# EYEO_Flower3_Sch.net
KiCad netlist of a schematic drawn in EAGLE
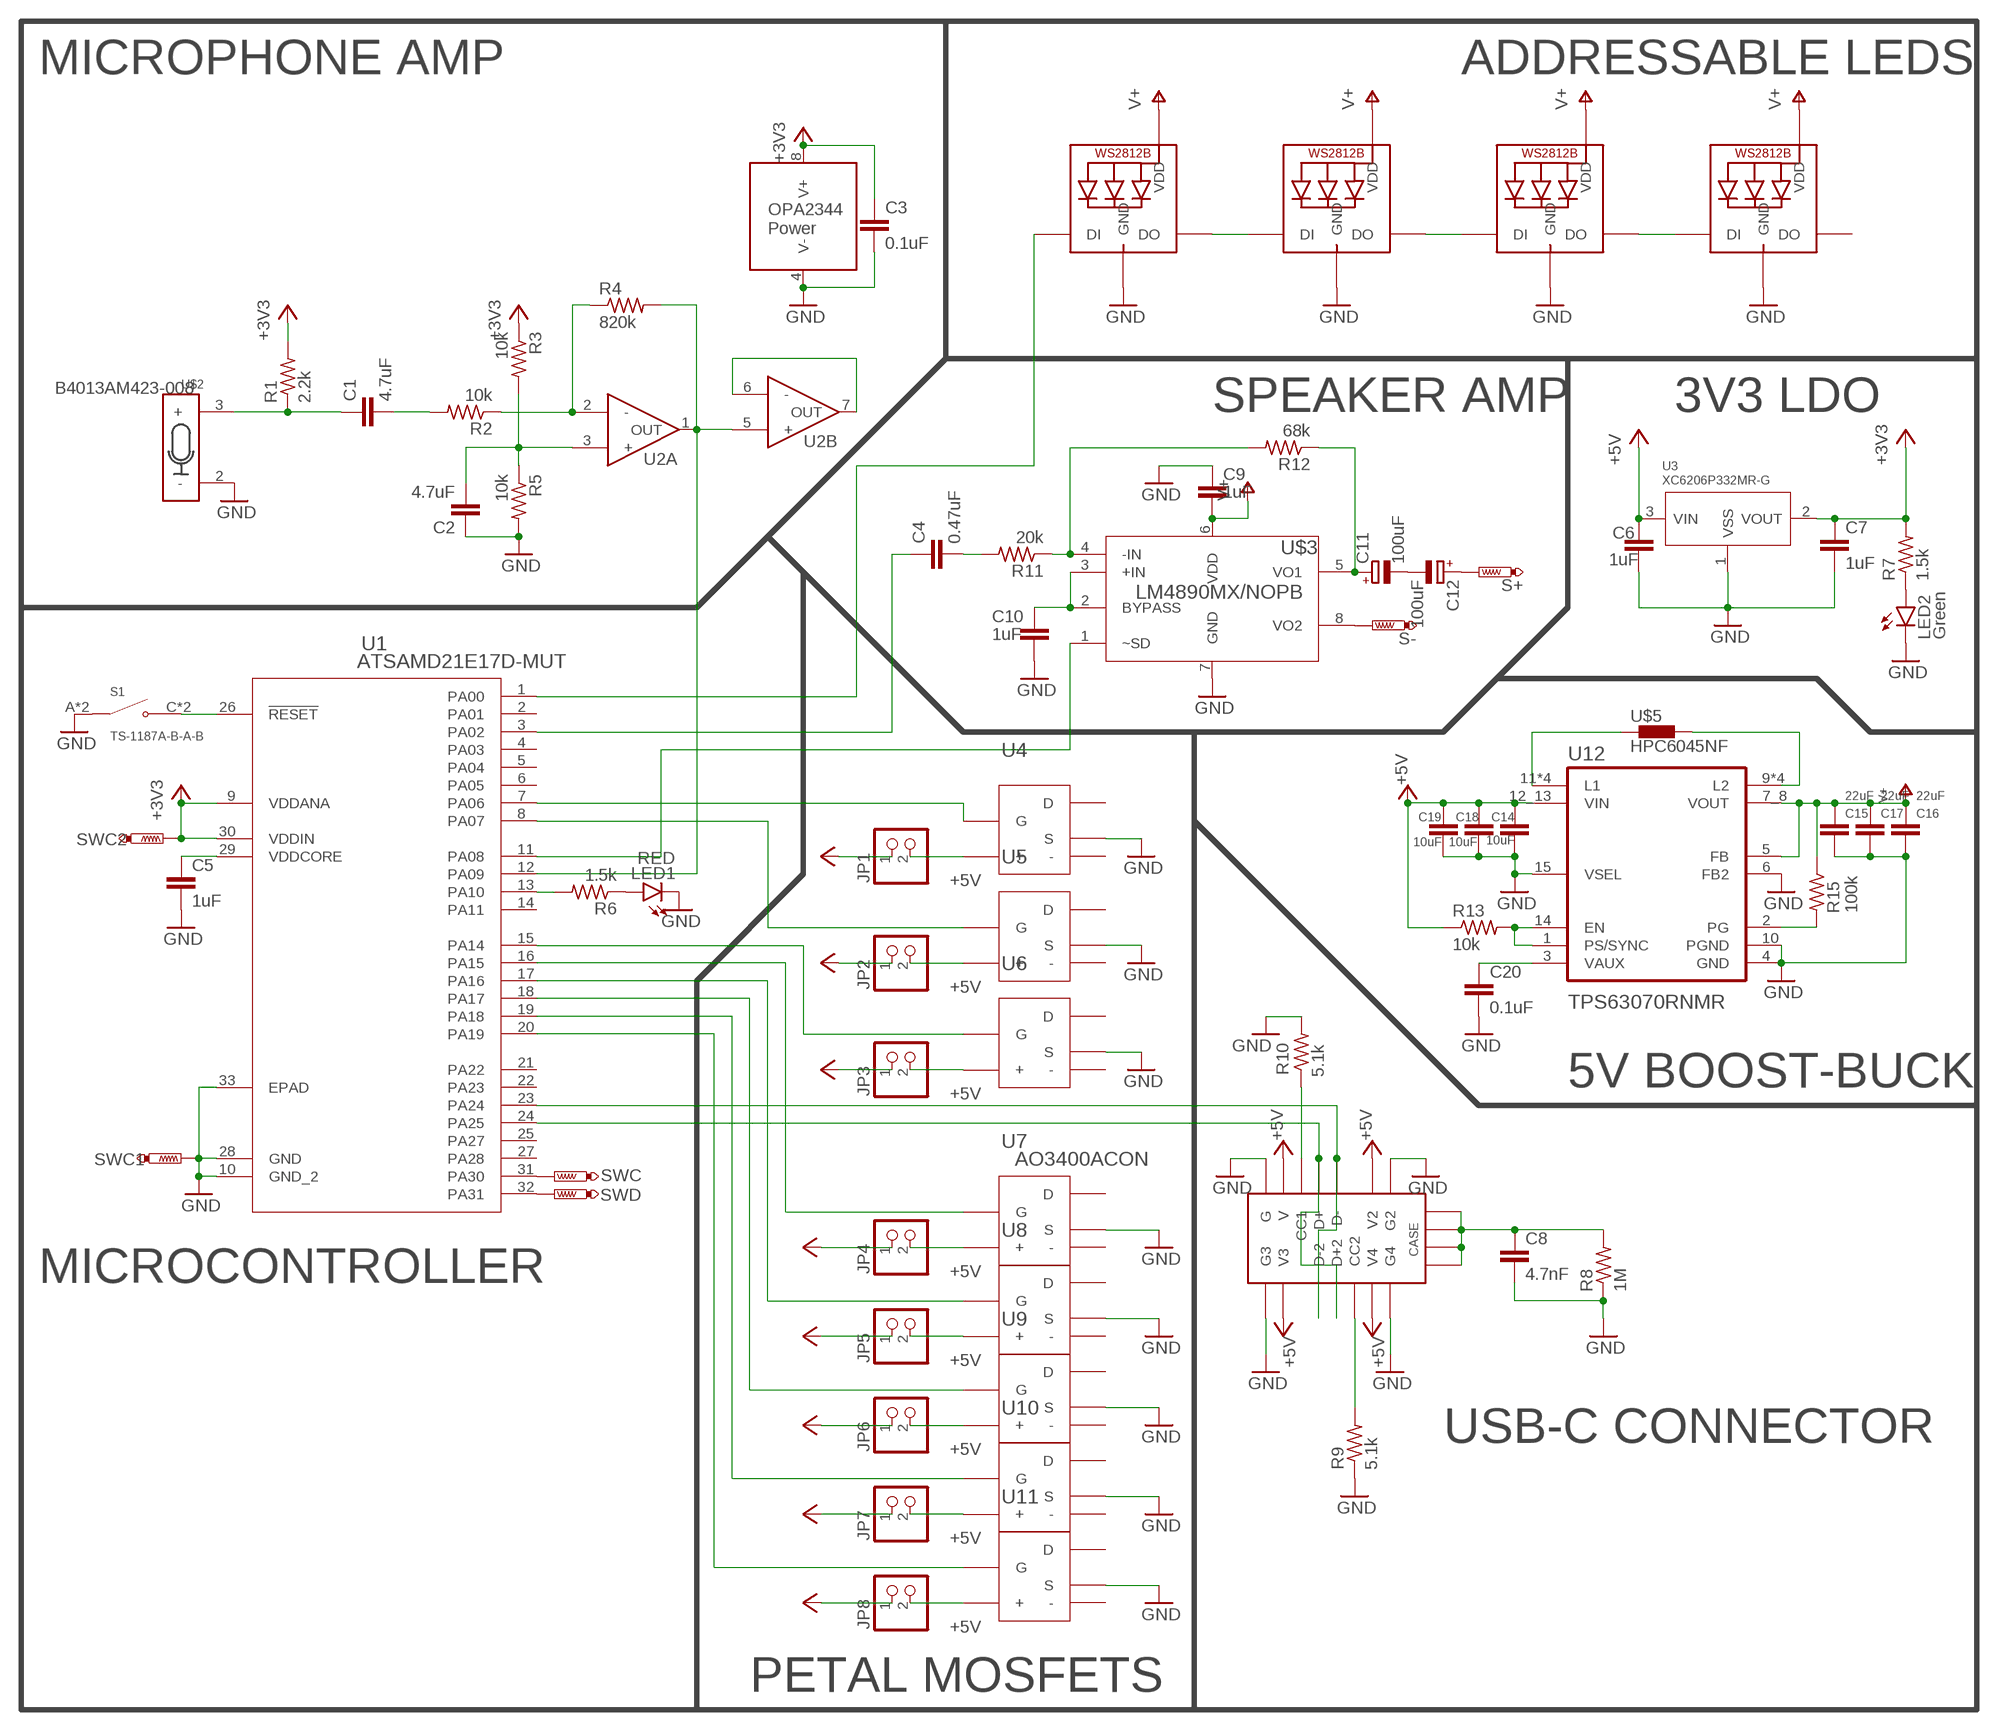
[diagram p0: schematic, sheet 1]

(export (version "E")
  (design (tool "Eeschema 10.0.6"))
  (components
    (comp (ref "C1")
      (value "4.7uF")
      (footprint "eagle-import:C0603")
      (fields (field (name "LCSC_PART") "C19666"))
      (libsource (lib "eagle-import") (part "C-EUC0603"))
    )
    (comp (ref "C2")
      (value "4.7uF")
      (footprint "eagle-import:C0603")
      (fields (field (name "LCSC_PART") "C19666"))
      (libsource (lib "eagle-import") (part "C-EUC0603"))
    )
    (comp (ref "C3")
      (value "0.1uF")
      (footprint "eagle-import:C0402")
      (fields (field (name "LCSC_PART") "C307331"))
      (libsource (lib "eagle-import") (part "C-EUC0402"))
    )
    (comp (ref "C4")
      (value "0.47uF")
      (footprint "eagle-import:C0603")
      (fields (field (name "LCSC_PART") "C1623"))
      (libsource (lib "eagle-import") (part "C-EUC0603"))
    )
    (comp (ref "C5")
      (value "1uF")
      (footprint "eagle-import:C0603")
      (fields (field (name "LCSC_PART") "C15849"))
      (libsource (lib "eagle-import") (part "C-EUC0603"))
    )
    (comp (ref "C6")
      (value "1uF")
      (footprint "eagle-import:C0603")
      (fields (field (name "LCSC_PART") "C15849"))
      (libsource (lib "eagle-import") (part "C-EUC0603"))
    )
    (comp (ref "C7")
      (value "1uF")
      (footprint "eagle-import:C0603")
      (fields (field (name "LCSC_PART") "C15849"))
      (libsource (lib "eagle-import") (part "C-EUC0603"))
    )
    (comp (ref "C8")
      (value "4.7nF")
      (footprint "eagle-import:C0402")
      (fields (field (name "LCSC_PART") "C1538"))
      (libsource (lib "eagle-import") (part "C-EUC0402"))
    )
    (comp (ref "C9")
      (value "1uF")
      (footprint "eagle-import:C0603")
      (fields (field (name "LCSC_PART") "C15849"))
      (libsource (lib "eagle-import") (part "C-EUC0603"))
    )
    (comp (ref "C10")
      (value "1uF")
      (footprint "eagle-import:C0603")
      (fields (field (name "LCSC_PART") "C15849"))
      (libsource (lib "eagle-import") (part "C-EUC0603"))
    )
    (comp (ref "C11")
      (value "100uF")
      (footprint "eagle-import:153CLV-0505")
      (fields (field (name "LCSC_PART") "C3347"))
      (libsource (lib "eagle-import") (part "CPOL-EU153CLV-0505"))
    )
    (comp (ref "C12")
      (value "100uF")
      (footprint "eagle-import:153CLV-0505")
      (fields (field (name "LCSC_PART") "C3347"))
      (libsource (lib "eagle-import") (part "CPOL-EU153CLV-0505"))
    )
    (comp (ref "C14")
      (value "10uF")
      (footprint "eagle-import:C0603")
      (fields (field (name "LCSC_PART") "C96446"))
      (libsource (lib "eagle-import") (part "C-EUC0603"))
    )
    (comp (ref "C15")
      (value "22uF")
      (footprint "eagle-import:C0603")
      (fields (field (name "LCSC_PART") "C59461"))
      (libsource (lib "eagle-import") (part "C-EUC0603"))
    )
    (comp (ref "C16")
      (value "22uF")
      (footprint "eagle-import:C0603")
      (fields (field (name "LCSC_PART") "C59461"))
      (libsource (lib "eagle-import") (part "C-EUC0603"))
    )
    (comp (ref "C17")
      (value "22uF")
      (footprint "eagle-import:C0603")
      (fields (field (name "LCSC_PART") "C59461"))
      (libsource (lib "eagle-import") (part "C-EUC0603"))
    )
    (comp (ref "C18")
      (value "10uF")
      (footprint "eagle-import:C0603")
      (fields (field (name "LCSC_PART") "C96446"))
      (libsource (lib "eagle-import") (part "C-EUC0603"))
    )
    (comp (ref "C19")
      (value "10uF")
      (footprint "eagle-import:C0603")
      (fields (field (name "LCSC_PART") "C96446"))
      (libsource (lib "eagle-import") (part "C-EUC0603"))
    )
    (comp (ref "C20")
      (value "0.1uF")
      (footprint "eagle-import:C0402")
      (fields (field (name "LCSC_PART") "C307331"))
      (libsource (lib "eagle-import") (part "C-EUC0402"))
    )
    (comp (ref "JP1")
      (value "PINHD-1X2")
      (footprint "eagle-import:1X02")
      (fields (field (name "LCSC_PART") "C2889984"))
      (libsource (lib "eagle-import") (part "PINHD-1X2"))
    )
    (comp (ref "JP2")
      (value "PINHD-1X2")
      (footprint "eagle-import:1X02")
      (fields (field (name "LCSC_PART") "C2889984"))
      (libsource (lib "eagle-import") (part "PINHD-1X2"))
    )
    (comp (ref "JP3")
      (value "PINHD-1X2")
      (footprint "eagle-import:1X02")
      (fields (field (name "LCSC_PART") "C2889984"))
      (libsource (lib "eagle-import") (part "PINHD-1X2"))
    )
    (comp (ref "JP4")
      (value "PINHD-1X2")
      (footprint "eagle-import:1X02")
      (fields (field (name "LCSC_PART") "C2889984"))
      (libsource (lib "eagle-import") (part "PINHD-1X2"))
    )
    (comp (ref "JP5")
      (value "PINHD-1X2")
      (footprint "eagle-import:1X02")
      (fields (field (name "LCSC_PART") "C2889984"))
      (libsource (lib "eagle-import") (part "PINHD-1X2"))
    )
    (comp (ref "JP6")
      (value "PINHD-1X2")
      (footprint "eagle-import:1X02")
      (fields (field (name "LCSC_PART") "C2889984"))
      (libsource (lib "eagle-import") (part "PINHD-1X2"))
    )
    (comp (ref "JP7")
      (value "PINHD-1X2")
      (footprint "eagle-import:1X02")
      (fields (field (name "LCSC_PART") "C2889984"))
      (libsource (lib "eagle-import") (part "PINHD-1X2"))
    )
    (comp (ref "JP8")
      (value "PINHD-1X2")
      (footprint "eagle-import:1X02")
      (fields (field (name "LCSC_PART") "C2889984"))
      (libsource (lib "eagle-import") (part "PINHD-1X2"))
    )
    (comp (ref "LED1")
      (value "RED")
      (footprint "eagle-import:CHIPLED_0805")
      (fields (field (name "LCSC_PART") "C84256"))
      (libsource (lib "eagle-import") (part "LEDCHIPLED_0805"))
    )
    (comp (ref "LED2")
      (value "Green")
      (footprint "eagle-import:CHIPLED_0603")
      (fields (field (name "LCSC_PART") "C72043"))
      (libsource (lib "eagle-import") (part "LEDCHIPLED_0603"))
    )
    (comp (ref "LED3")
      (value "WS2812B5050")
      (footprint "eagle-import:WS2812B")
      (fields
        (field (name "LCSC_PART") "C2761795")
        (field (name "MF") "Worldsemi")
        (field (name "MP") "WS2812B")
      )
      (libsource (lib "eagle-import") (part "WS2812B5050"))
    )
    (comp (ref "LED4")
      (value "WS2812B5050")
      (footprint "eagle-import:WS2812B")
      (fields
        (field (name "LCSC_PART") "C2761795")
        (field (name "MF") "Worldsemi")
        (field (name "MP") "WS2812B")
      )
      (libsource (lib "eagle-import") (part "WS2812B5050"))
    )
    (comp (ref "LED5")
      (value "WS2812B5050")
      (footprint "eagle-import:WS2812B")
      (fields
        (field (name "LCSC_PART") "C2761795")
        (field (name "MF") "Worldsemi")
        (field (name "MP") "WS2812B")
      )
      (libsource (lib "eagle-import") (part "WS2812B5050"))
    )
    (comp (ref "LED6")
      (value "WS2812B5050")
      (footprint "eagle-import:WS2812B")
      (fields
        (field (name "LCSC_PART") "C2761795")
        (field (name "MF") "Worldsemi")
        (field (name "MP") "WS2812B")
      )
      (libsource (lib "eagle-import") (part "WS2812B5050"))
    )
    (comp (ref "R1")
      (value "2.2k")
      (footprint "eagle-import:R0402")
      (fields (field (name "LCSC_PART") "C25879"))
      (libsource (lib "eagle-import") (part "R-US_R0402"))
    )
    (comp (ref "R2")
      (value "10k")
      (footprint "eagle-import:R0402")
      (fields (field (name "LCSC_PART") "C25744"))
      (libsource (lib "eagle-import") (part "R-US_R0402"))
    )
    (comp (ref "R3")
      (value "10k")
      (footprint "eagle-import:R0402")
      (fields (field (name "LCSC_PART") "C25744"))
      (libsource (lib "eagle-import") (part "R-US_R0402"))
    )
    (comp (ref "R4")
      (value "820k")
      (footprint "eagle-import:R0402")
      (fields (field (name "LCSC_PART") "C67558"))
      (libsource (lib "eagle-import") (part "R-US_R0402"))
    )
    (comp (ref "R5")
      (value "10k")
      (footprint "eagle-import:R0402")
      (fields (field (name "LCSC_PART") "C25744"))
      (libsource (lib "eagle-import") (part "R-US_R0402"))
    )
    (comp (ref "R6")
      (value "1.5k")
      (footprint "eagle-import:R0402")
      (fields (field (name "LCSC_PART") "C25867"))
      (libsource (lib "eagle-import") (part "R-US_R0402"))
    )
    (comp (ref "R7")
      (value "1.5k")
      (footprint "eagle-import:R0402")
      (fields (field (name "LCSC_PART") "C25867"))
      (libsource (lib "eagle-import") (part "R-US_R0402"))
    )
    (comp (ref "R8")
      (value "1M")
      (footprint "eagle-import:R0402")
      (fields (field (name "LCSC_PART") "C26083"))
      (libsource (lib "eagle-import") (part "R-US_R0402"))
    )
    (comp (ref "R9")
      (value "5.1k")
      (footprint "eagle-import:R0402")
      (fields (field (name "LCSC_PART") "C25905"))
      (libsource (lib "eagle-import") (part "R-US_R0402"))
    )
    (comp (ref "R10")
      (value "5.1k")
      (footprint "eagle-import:R0402")
      (fields (field (name "LCSC_PART") "C25905"))
      (libsource (lib "eagle-import") (part "R-US_R0402"))
    )
    (comp (ref "R11")
      (value "20k")
      (footprint "eagle-import:R0402")
      (fields (field (name "LCSC_PART") "C25765"))
      (libsource (lib "eagle-import") (part "R-US_R0402"))
    )
    (comp (ref "R12")
      (value "68k")
      (footprint "eagle-import:R0402")
      (fields (field (name "LCSC_PART") "C36871"))
      (libsource (lib "eagle-import") (part "R-US_R0402"))
    )
    (comp (ref "R13")
      (value "10k")
      (footprint "eagle-import:R0402")
      (fields (field (name "LCSC_PART") "C25744"))
      (libsource (lib "eagle-import") (part "R-US_R0402"))
    )
    (comp (ref "R15")
      (value "100k")
      (footprint "eagle-import:R0402")
      (fields (field (name "LCSC_PART") "C25741"))
      (libsource (lib "eagle-import") (part "R-US_R0402"))
    )
    (comp (ref "S+")
      (value "PTR11MM")
      (footprint "eagle-import:1MM")
      (fields (field (name "LCSC_PART") "C238122"))
      (libsource (lib "eagle-import") (part "PTR11MM"))
    )
    (comp (ref "S-")
      (value "PTR11MM")
      (footprint "eagle-import:1MM")
      (fields (field (name "LCSC_PART") "C238122"))
      (libsource (lib "eagle-import") (part "PTR11MM"))
    )
    (comp (ref "S1")
      (value "TS-1187A-B-A-B")
      (footprint "eagle-import:SW_TS-1187A-B-A-B")
      (fields (field (name "MF") "XKB Industrial Precision") (field (name "LCSC_PART") "C318884"))
      (libsource (lib "eagle-import") (part "TS-1187A-B-A-B"))
    )
    (comp (ref "SWC")
      (value "PTR1PAD1-13")
      (footprint "eagle-import:P1-13")
      (libsource (lib "eagle-import") (part "PTR1PAD1-13"))
    )
    (comp (ref "SWC1")
      (value "PTR1PAD1-13")
      (footprint "eagle-import:P1-13")
      (libsource (lib "eagle-import") (part "PTR1PAD1-13"))
    )
    (comp (ref "SWC2")
      (value "PTR1PAD1-13")
      (footprint "eagle-import:P1-13")
      (libsource (lib "eagle-import") (part "PTR1PAD1-13"))
    )
    (comp (ref "SWD")
      (value "PTR1PAD1-13")
      (footprint "eagle-import:P1-13")
      (libsource (lib "eagle-import") (part "PTR1PAD1-13"))
    )
    (comp (ref "U$1")
      (value "USB-C")
      (footprint "eagle-import:918-418K2022Y40000")
      (fields (field (name "LCSC_PART") "C168704"))
      (libsource (lib "eagle-import") (part "USB-C"))
    )
    (comp (ref "U$2")
      (value "B4013AM423")
      (footprint "eagle-import:B4013AM423")
      (fields (field (name "LCSC_PART") "C233794") (field (name "NUM") "B4013AM423-008 "))
      (libsource (lib "eagle-import") (part "B4013AM423"))
    )
    (comp (ref "U$3")
      (value "LM4890MX/NOPB")
      (footprint "eagle-import:M08A")
      (fields
        (field (name "LCSC_PART") "C117476")
        (field (name "COPYRIGHT") "Copyright (C) 2022 Ultra Librarian. All rights reserved.")
      )
      (libsource (lib "eagle-import") (part "LM4890MX/NOPB"))
    )
    (comp (ref "U$5")
      (value "HPC6045NF")
      (footprint "eagle-import:HPC6045NF")
      (fields (field (name "LCSC_PART") "C357076"))
      (libsource (lib "eagle-import") (part "HPC6045NF"))
    )
    (comp (ref "U1")
      (value "ATSAMD21E17D-MUT")
      (footprint "eagle-import:QFN32_5X5MC_MCH")
      (fields (field (name "COPYRIGHT") "Copyright (C) 2022 Ultra Librarian. All rights reserved."))
      (libsource (lib "eagle-import") (part "ATSAMD21E17D-MUT"))
    )
    (comp (ref "U2")
      (value "OPA2344UA")
      (footprint "eagle-import:D8")
      (fields
        (field (name "LCSC_PART") "C202213")
        (field (name "COPYRIGHT") "Copyright (C) 2022 Ultra Librarian. All rights reserved.")
      )
      (libsource (lib "eagle-import") (part "OPA2344UA"))
    )
    (comp (ref "U3")
      (value "XC6206P332MR-G")
      (footprint "eagle-import:SOT-23")
      (fields (field (name "MF") "Torex") (field (name "LCSC_PART") "C5446"))
      (libsource (lib "eagle-import") (part "PMIC-LDO-XC6206P332MR-G(SOT23)"))
    )
    (comp (ref "U4")
      (value "AO3400ACON")
      (footprint "eagle-import:SOT23-BCE-CON")
      (fields (field (name "LCSC_PART") "C20917"))
      (libsource (lib "eagle-import") (part "AO3400ACON"))
    )
    (comp (ref "U5")
      (value "AO3400ACON")
      (footprint "eagle-import:SOT23-BCE-CON")
      (fields (field (name "LCSC_PART") "C20917"))
      (libsource (lib "eagle-import") (part "AO3400ACON"))
    )
    (comp (ref "U6")
      (value "AO3400ACON")
      (footprint "eagle-import:SOT23-BCE-CON")
      (fields (field (name "LCSC_PART") "C20917"))
      (libsource (lib "eagle-import") (part "AO3400ACON"))
    )
    (comp (ref "U7")
      (value "AO3400ACON")
      (footprint "eagle-import:SOT23-BCE-CON")
      (fields (field (name "LCSC_PART") "C20917"))
      (libsource (lib "eagle-import") (part "AO3400ACON"))
    )
    (comp (ref "U8")
      (value "AO3400ACON")
      (footprint "eagle-import:SOT23-BCE-CON")
      (fields (field (name "LCSC_PART") "C20917"))
      (libsource (lib "eagle-import") (part "AO3400ACON"))
    )
    (comp (ref "U9")
      (value "AO3400ACON")
      (footprint "eagle-import:SOT23-BCE-CON")
      (fields (field (name "LCSC_PART") "C20917"))
      (libsource (lib "eagle-import") (part "AO3400ACON"))
    )
    (comp (ref "U10")
      (value "AO3400ACON")
      (footprint "eagle-import:SOT23-BCE-CON")
      (fields (field (name "LCSC_PART") "C20917"))
      (libsource (lib "eagle-import") (part "AO3400ACON"))
    )
    (comp (ref "U11")
      (value "AO3400ACON")
      (footprint "eagle-import:SOT23-BCE-CON")
      (fields (field (name "LCSC_PART") "C20917"))
      (libsource (lib "eagle-import") (part "AO3400ACON"))
    )
    (comp (ref "U12")
      (value "TPS63070RNMR")
      (footprint "eagle-import:VREG_TPS63070RNMR")
      (fields (field (name "LCSC_PART") "C2876599") (field (name "MF") "Texas Instruments"))
      (libsource (lib "eagle-import") (part "TPS63070RNMR"))
    )
  )
  (nets
    (net (code "1") (name "+3V3") (class "Default")
      (node (ref "C3") (pin "1") (pinfunction "1_1") (pintype "passive"))
      (node (ref "C7") (pin "1") (pinfunction "1_1") (pintype "passive"))
      (node (ref "R1") (pin "2") (pinfunction "2_2") (pintype "passive"))
      (node (ref "R3") (pin "1") (pinfunction "1_1") (pintype "passive"))
      (node (ref "R7") (pin "2") (pinfunction "2_2") (pintype "passive"))
      (node (ref "SWC2") (pin "TP") (pinfunction "TP_TP") (pintype "input"))
      (node (ref "U1") (pin "30") (pinfunction "VDDIN_30") (pintype "power_in"))
      (node (ref "U1") (pin "9") (pinfunction "VDDANA_9") (pintype "power_in"))
      (node (ref "U2") (pin "8") (pinfunction "V+_8") (pintype "bidirectional"))
      (node (ref "U3") (pin "2") (pinfunction "VOUT_2") (pintype "output"))
    )
    (net (code "2") (name "+5V") (class "Default")
      (node (ref "C14") (pin "1") (pinfunction "1_1") (pintype "passive"))
      (node (ref "C18") (pin "1") (pinfunction "1_1") (pintype "passive"))
      (node (ref "C19") (pin "1") (pinfunction "1_1") (pintype "passive"))
      (node (ref "C6") (pin "1") (pinfunction "1_1") (pintype "passive"))
      (node (ref "JP1") (pin "1") (pinfunction "1_1") (pintype "passive"))
      (node (ref "JP2") (pin "1") (pinfunction "1_1") (pintype "passive"))
      (node (ref "JP3") (pin "1") (pinfunction "1_1") (pintype "passive"))
      (node (ref "JP4") (pin "1") (pinfunction "1_1") (pintype "passive"))
      (node (ref "JP5") (pin "1") (pinfunction "1_1") (pintype "passive"))
      (node (ref "JP6") (pin "1") (pinfunction "1_1") (pintype "passive"))
      (node (ref "JP7") (pin "1") (pinfunction "1_1") (pintype "passive"))
      (node (ref "JP8") (pin "1") (pinfunction "1_1") (pintype "passive"))
      (node (ref "R13") (pin "1") (pinfunction "1_1") (pintype "passive"))
      (node (ref "U$1") (pin "V") (pinfunction "V_V") (pintype "bidirectional"))
      (node (ref "U$1") (pin "V2") (pinfunction "V2_V2") (pintype "bidirectional"))
      (node (ref "U$1") (pin "V3") (pinfunction "V3_V3") (pintype "bidirectional"))
      (node (ref "U$1") (pin "V4") (pinfunction "V4_V4") (pintype "bidirectional"))
      (node (ref "U12") (pin "12_13") (pinfunction "VIN_12_13") (pintype "input"))
      (node (ref "U3") (pin "3") (pinfunction "VIN_3") (pintype "input"))
    )
    (net (code "3") (name "GND") (class "Default")
      (node (ref "C10") (pin "2") (pinfunction "2_2") (pintype "passive"))
      (node (ref "C14") (pin "2") (pinfunction "2_2") (pintype "passive"))
      (node (ref "C15") (pin "2") (pinfunction "2_2") (pintype "passive"))
      (node (ref "C16") (pin "2") (pinfunction "2_2") (pintype "passive"))
      (node (ref "C17") (pin "2") (pinfunction "2_2") (pintype "passive"))
      (node (ref "C18") (pin "2") (pinfunction "2_2") (pintype "passive"))
      (node (ref "C19") (pin "2") (pinfunction "2_2") (pintype "passive"))
      (node (ref "C2") (pin "1") (pinfunction "1_1") (pintype "passive"))
      (node (ref "C20") (pin "2") (pinfunction "2_2") (pintype "passive"))
      (node (ref "C3") (pin "2") (pinfunction "2_2") (pintype "passive"))
      (node (ref "C5") (pin "2") (pinfunction "2_2") (pintype "passive"))
      (node (ref "C6") (pin "2") (pinfunction "2_2") (pintype "passive"))
      (node (ref "C7") (pin "2") (pinfunction "2_2") (pintype "passive"))
      (node (ref "C8") (pin "2") (pinfunction "2_2") (pintype "passive"))
      (node (ref "C9") (pin "1") (pinfunction "1_1") (pintype "passive"))
      (node (ref "LED1") (pin "C") (pinfunction "C_C") (pintype "passive"))
      (node (ref "LED2") (pin "C") (pinfunction "C_C") (pintype "passive"))
      (node (ref "LED3") (pin "3-GND") (pinfunction "GND_3-GND") (pintype "power_in"))
      (node (ref "LED4") (pin "3-GND") (pinfunction "GND_3-GND") (pintype "power_in"))
      (node (ref "LED5") (pin "3-GND") (pinfunction "GND_3-GND") (pintype "power_in"))
      (node (ref "LED6") (pin "3-GND") (pinfunction "GND_3-GND") (pintype "power_in"))
      (node (ref "R10") (pin "2") (pinfunction "2_2") (pintype "passive"))
      (node (ref "R5") (pin "2") (pinfunction "2_2") (pintype "passive"))
      (node (ref "R8") (pin "1") (pinfunction "1_1") (pintype "passive"))
      (node (ref "R9") (pin "1") (pinfunction "1_1") (pintype "passive"))
      (node (ref "S1") (pin "A") (pinfunction "COM_A") (pintype "passive"))
      (node (ref "S1") (pin "B") (pinfunction "COM_B") (pintype "passive"))
      (node (ref "SWC1") (pin "TP") (pinfunction "TP_TP") (pintype "input"))
      (node (ref "U$1") (pin "G") (pinfunction "G_G") (pintype "bidirectional"))
      (node (ref "U$1") (pin "G2") (pinfunction "G2_G2") (pintype "bidirectional"))
      (node (ref "U$1") (pin "G3") (pinfunction "G3_G3") (pintype "bidirectional"))
      (node (ref "U$1") (pin "G4") (pinfunction "G4_G4") (pintype "bidirectional"))
      (node (ref "U$2") (pin "2") (pinfunction "-_2") (pintype "bidirectional"))
      (node (ref "U$3") (pin "7") (pinfunction "GND_7") (pintype "power_in"))
      (node (ref "U1") (pin "10") (pinfunction "GND_2_10") (pintype "passive"))
      (node (ref "U1") (pin "28") (pinfunction "GND_28") (pintype "passive"))
      (node (ref "U1") (pin "33") (pinfunction "EPAD_33") (pintype "passive"))
      (node (ref "U10") (pin "S") (pinfunction "S_S") (pintype "passive"))
      (node (ref "U11") (pin "S") (pinfunction "S_S") (pintype "passive"))
      (node (ref "U12") (pin "10") (pinfunction "PGND_10") (pintype "power_in"))
      (node (ref "U12") (pin "15") (pinfunction "VSEL_15") (pintype "input"))
      (node (ref "U12") (pin "4") (pinfunction "GND_4") (pintype "power_in"))
      (node (ref "U12") (pin "6") (pinfunction "FB2_6") (pintype "output"))
      (node (ref "U2") (pin "4") (pinfunction "V-_4") (pintype "bidirectional"))
      (node (ref "U3") (pin "1") (pinfunction "VSS_1") (pintype "power_in"))
      (node (ref "U4") (pin "S") (pinfunction "S_S") (pintype "passive"))
      (node (ref "U5") (pin "S") (pinfunction "S_S") (pintype "passive"))
      (node (ref "U6") (pin "S") (pinfunction "S_S") (pintype "passive"))
      (node (ref "U7") (pin "S") (pinfunction "S_S") (pintype "passive"))
      (node (ref "U8") (pin "S") (pinfunction "S_S") (pintype "passive"))
      (node (ref "U9") (pin "S") (pinfunction "S_S") (pintype "passive"))
    )
    (net (code "4") (name "Net-(C1-Pad2)") (class "Default")
      (node (ref "C1") (pin "2") (pinfunction "2_2") (pintype "passive"))
      (node (ref "R2") (pin "2") (pinfunction "2_2") (pintype "passive"))
    )
    (net (code "5") (name "Net-(C4-Pad2)") (class "Default")
      (node (ref "C4") (pin "2") (pinfunction "2_2") (pintype "passive"))
      (node (ref "R11") (pin "2") (pinfunction "2_2") (pintype "passive"))
    )
    (net (code "6") (name "Net-(C11-Pad-)") (class "Default")
      (node (ref "C11") (pin "-") (pinfunction "-_-") (pintype "passive"))
      (node (ref "C12") (pin "-") (pinfunction "-_-") (pintype "passive"))
    )
    (net (code "7") (name "Net-(C12-Pad+)") (class "Default")
      (node (ref "C12") (pin "+") (pinfunction "+_+") (pintype "passive"))
      (node (ref "S+") (pin "TP") (pinfunction "TP_TP") (pintype "input"))
    )
    (net (code "8") (name "Net-(JP1-Pad2)") (class "Default")
      (node (ref "JP1") (pin "2") (pinfunction "2_2") (pintype "passive"))
      (node (ref "U4") (pin "+") (pinfunction "+_+") (pintype "bidirectional"))
    )
    (net (code "9") (name "Net-(JP2-Pad2)") (class "Default")
      (node (ref "JP2") (pin "2") (pinfunction "2_2") (pintype "passive"))
      (node (ref "U5") (pin "+") (pinfunction "+_+") (pintype "bidirectional"))
    )
    (net (code "10") (name "Net-(JP3-Pad2)") (class "Default")
      (node (ref "JP3") (pin "2") (pinfunction "2_2") (pintype "passive"))
      (node (ref "U6") (pin "+") (pinfunction "+_+") (pintype "bidirectional"))
    )
    (net (code "11") (name "Net-(JP4-Pad2)") (class "Default")
      (node (ref "JP4") (pin "2") (pinfunction "2_2") (pintype "passive"))
      (node (ref "U7") (pin "+") (pinfunction "+_+") (pintype "bidirectional"))
    )
    (net (code "12") (name "Net-(JP5-Pad2)") (class "Default")
      (node (ref "JP5") (pin "2") (pinfunction "2_2") (pintype "passive"))
      (node (ref "U8") (pin "+") (pinfunction "+_+") (pintype "bidirectional"))
    )
    (net (code "13") (name "Net-(JP6-Pad2)") (class "Default")
      (node (ref "JP6") (pin "2") (pinfunction "2_2") (pintype "passive"))
      (node (ref "U9") (pin "+") (pinfunction "+_+") (pintype "bidirectional"))
    )
    (net (code "14") (name "Net-(JP7-Pad2)") (class "Default")
      (node (ref "JP7") (pin "2") (pinfunction "2_2") (pintype "passive"))
      (node (ref "U10") (pin "+") (pinfunction "+_+") (pintype "bidirectional"))
    )
    (net (code "15") (name "Net-(JP8-Pad2)") (class "Default")
      (node (ref "JP8") (pin "2") (pinfunction "2_2") (pintype "passive"))
      (node (ref "U11") (pin "+") (pinfunction "+_+") (pintype "bidirectional"))
    )
    (net (code "16") (name "Net-(LED1-PadA)") (class "Default")
      (node (ref "LED1") (pin "A") (pinfunction "A_A") (pintype "passive"))
      (node (ref "R6") (pin "1") (pinfunction "1_1") (pintype "passive"))
    )
    (net (code "17") (name "Net-(LED2-PadA)") (class "Default")
      (node (ref "LED2") (pin "A") (pinfunction "A_A") (pintype "passive"))
      (node (ref "R7") (pin "1") (pinfunction "1_1") (pintype "passive"))
    )
    (net (code "18") (name "Net-(LED3-DI)") (class "Default")
      (node (ref "LED3") (pin "4-DIN") (pinfunction "DI_4-DIN") (pintype "input"))
      (node (ref "U1") (pin "1") (pinfunction "PA00_1") (pintype "bidirectional"))
    )
    (net (code "19") (name "Net-(LED3-DO)") (class "Default")
      (node (ref "LED3") (pin "2-DOUT") (pinfunction "DO_2-DOUT") (pintype "output"))
      (node (ref "LED4") (pin "4-DIN") (pinfunction "DI_4-DIN") (pintype "input"))
    )
    (net (code "20") (name "Net-(LED4-DO)") (class "Default")
      (node (ref "LED4") (pin "2-DOUT") (pinfunction "DO_2-DOUT") (pintype "output"))
      (node (ref "LED5") (pin "4-DIN") (pinfunction "DI_4-DIN") (pintype "input"))
    )
    (net (code "21") (name "Net-(LED5-DO)") (class "Default")
      (node (ref "LED5") (pin "2-DOUT") (pinfunction "DO_2-DOUT") (pintype "output"))
      (node (ref "LED6") (pin "4-DIN") (pinfunction "DI_4-DIN") (pintype "input"))
    )
    (net (code "22") (name "Net-(R9-Pad2)") (class "Default")
      (node (ref "R9") (pin "2") (pinfunction "2_2") (pintype "passive"))
      (node (ref "U$1") (pin "CC2") (pinfunction "CC2_CC2") (pintype "bidirectional"))
    )
    (net (code "23") (name "Net-(R10-Pad1)") (class "Default")
      (node (ref "R10") (pin "1") (pinfunction "1_1") (pintype "passive"))
      (node (ref "U$1") (pin "CC1") (pinfunction "CC1_CC1") (pintype "bidirectional"))
    )
    (net (code "24") (name "Net-(U$1-1)") (class "Default")
      (node (ref "C8") (pin "1") (pinfunction "1_1") (pintype "passive"))
      (node (ref "R8") (pin "2") (pinfunction "2_2") (pintype "passive"))
      (node (ref "U$1") (pin "OG1") (pinfunction "1_OG1") (pintype "bidirectional"))
      (node (ref "U$1") (pin "OG2") (pinfunction "2_OG2") (pintype "bidirectional"))
      (node (ref "U$1") (pin "OG3") (pinfunction "3_OG3") (pintype "bidirectional"))
      (node (ref "U$1") (pin "OG4") (pinfunction "4_OG4") (pintype "bidirectional"))
    )
    (net (code "25") (name "Net-(U$2-+)") (class "Default")
      (node (ref "C1") (pin "1") (pinfunction "1_1") (pintype "passive"))
      (node (ref "R1") (pin "1") (pinfunction "1_1") (pintype "passive"))
      (node (ref "U$2") (pin "3") (pinfunction "+_3") (pintype "bidirectional"))
    )
    (net (code "26") (name "Net-(U$3-+IN)") (class "Default")
      (node (ref "C10") (pin "1") (pinfunction "1_1") (pintype "passive"))
      (node (ref "U$3") (pin "2") (pinfunction "BYPASS_2") (pintype "passive"))
      (node (ref "U$3") (pin "3") (pinfunction "+IN_3") (pintype "input"))
    )
    (net (code "27") (name "Net-(U$3--IN)") (class "Default")
      (node (ref "R11") (pin "1") (pinfunction "1_1") (pintype "passive"))
      (node (ref "R12") (pin "2") (pinfunction "2_2") (pintype "passive"))
      (node (ref "U$3") (pin "4") (pinfunction "-IN_4") (pintype "input"))
    )
    (net (code "28") (name "Net-(U$3-VO1)") (class "Default")
      (node (ref "C11") (pin "+") (pinfunction "+_+") (pintype "passive"))
      (node (ref "R12") (pin "1") (pinfunction "1_1") (pintype "passive"))
      (node (ref "U$3") (pin "5") (pinfunction "VO1_5") (pintype "output"))
    )
    (net (code "29") (name "Net-(U$3-VO2)") (class "Default")
      (node (ref "S-") (pin "TP") (pinfunction "TP_TP") (pintype "input"))
      (node (ref "U$3") (pin "8") (pinfunction "VO2_8") (pintype "output"))
    )
    (net (code "30") (name "Net-(U$3-~{SD})") (class "Default")
      (node (ref "U$3") (pin "1") (pinfunction "~{SD}_1") (pintype "input"))
      (node (ref "U1") (pin "11") (pinfunction "PA08_11") (pintype "bidirectional"))
    )
    (net (code "31") (name "Net-(U$5-1)") (class "Default")
      (node (ref "U$5") (pin "P$1") (pinfunction "1_P$1") (pintype "passive"))
      (node (ref "U12") (pin "11") (pinfunction "L1_11") (pintype "bidirectional"))
      (node (ref "U12") (pin "11_1") (pinfunction "L1_11_1") (pintype "bidirectional"))
      (node (ref "U12") (pin "11_2") (pinfunction "L1_11_2") (pintype "bidirectional"))
      (node (ref "U12") (pin "11_3") (pinfunction "L1_11_3") (pintype "bidirectional"))
    )
    (net (code "32") (name "Net-(U$5-2)") (class "Default")
      (node (ref "U$5") (pin "P$2") (pinfunction "2_P$2") (pintype "passive"))
      (node (ref "U12") (pin "9") (pinfunction "L2_9") (pintype "bidirectional"))
      (node (ref "U12") (pin "9_1") (pinfunction "L2_9_1") (pintype "bidirectional"))
      (node (ref "U12") (pin "9_2") (pinfunction "L2_9_2") (pintype "bidirectional"))
      (node (ref "U12") (pin "9_3") (pinfunction "L2_9_3") (pintype "bidirectional"))
    )
    (net (code "33") (name "Net-(U1-PA02)") (class "Default")
      (node (ref "C4") (pin "1") (pinfunction "1_1") (pintype "passive"))
      (node (ref "U1") (pin "3") (pinfunction "PA02_3") (pintype "bidirectional"))
    )
    (net (code "34") (name "Net-(U1-PA06)") (class "Default")
      (node (ref "U1") (pin "7") (pinfunction "PA06_7") (pintype "bidirectional"))
      (node (ref "U4") (pin "G") (pinfunction "G_G") (pintype "passive"))
    )
    (net (code "35") (name "Net-(U1-PA07)") (class "Default")
      (node (ref "U1") (pin "8") (pinfunction "PA07_8") (pintype "bidirectional"))
      (node (ref "U5") (pin "G") (pinfunction "G_G") (pintype "passive"))
    )
    (net (code "36") (name "Net-(U1-PA09)") (class "Default")
      (node (ref "R4") (pin "2") (pinfunction "2_2") (pintype "passive"))
      (node (ref "U1") (pin "12") (pinfunction "PA09_12") (pintype "bidirectional"))
      (node (ref "U2") (pin "1") (pinfunction "OUT_1") (pintype "bidirectional"))
      (node (ref "U2") (pin "5") (pinfunction "+_5") (pintype "bidirectional"))
    )
    (net (code "37") (name "Net-(U1-PA10)") (class "Default")
      (node (ref "R6") (pin "2") (pinfunction "2_2") (pintype "passive"))
      (node (ref "U1") (pin "13") (pinfunction "PA10_13") (pintype "bidirectional"))
    )
    (net (code "38") (name "Net-(U1-PA14)") (class "Default")
      (node (ref "U1") (pin "15") (pinfunction "PA14_15") (pintype "bidirectional"))
      (node (ref "U6") (pin "G") (pinfunction "G_G") (pintype "passive"))
    )
    (net (code "39") (name "Net-(U1-PA15)") (class "Default")
      (node (ref "U1") (pin "16") (pinfunction "PA15_16") (pintype "bidirectional"))
      (node (ref "U7") (pin "G") (pinfunction "G_G") (pintype "passive"))
    )
    (net (code "40") (name "Net-(U1-PA16)") (class "Default")
      (node (ref "U1") (pin "17") (pinfunction "PA16_17") (pintype "bidirectional"))
      (node (ref "U8") (pin "G") (pinfunction "G_G") (pintype "passive"))
    )
    (net (code "41") (name "Net-(U1-PA17)") (class "Default")
      (node (ref "U1") (pin "18") (pinfunction "PA17_18") (pintype "bidirectional"))
      (node (ref "U9") (pin "G") (pinfunction "G_G") (pintype "passive"))
    )
    (net (code "42") (name "Net-(U1-PA18)") (class "Default")
      (node (ref "U1") (pin "19") (pinfunction "PA18_19") (pintype "bidirectional"))
      (node (ref "U10") (pin "G") (pinfunction "G_G") (pintype "passive"))
    )
    (net (code "43") (name "Net-(U1-PA19)") (class "Default")
      (node (ref "U1") (pin "20") (pinfunction "PA19_20") (pintype "bidirectional"))
      (node (ref "U11") (pin "G") (pinfunction "G_G") (pintype "passive"))
    )
    (net (code "44") (name "Net-(U1-PA24)") (class "Default")
      (node (ref "U$1") (pin "D-") (pinfunction "D-_D-") (pintype "bidirectional"))
      (node (ref "U$1") (pin "D-2") (pinfunction "D-2_D-2") (pintype "bidirectional"))
      (node (ref "U1") (pin "23") (pinfunction "PA24_23") (pintype "bidirectional"))
    )
    (net (code "45") (name "Net-(U1-PA25)") (class "Default")
      (node (ref "U$1") (pin "D+") (pinfunction "D+_D+") (pintype "bidirectional"))
      (node (ref "U$1") (pin "D+2") (pinfunction "D+2_D+2") (pintype "bidirectional"))
      (node (ref "U1") (pin "24") (pinfunction "PA25_24") (pintype "bidirectional"))
    )
    (net (code "46") (name "Net-(U1-PA30)") (class "Default")
      (node (ref "SWC") (pin "TP") (pinfunction "TP_TP") (pintype "input"))
      (node (ref "U1") (pin "31") (pinfunction "PA30_31") (pintype "bidirectional"))
    )
    (net (code "47") (name "Net-(U1-PA31)") (class "Default")
      (node (ref "SWD") (pin "TP") (pinfunction "TP_TP") (pintype "input"))
      (node (ref "U1") (pin "32") (pinfunction "PA31_32") (pintype "bidirectional"))
    )
    (net (code "48") (name "Net-(U1-VDDCORE)") (class "Default")
      (node (ref "C5") (pin "1") (pinfunction "1_1") (pintype "passive"))
      (node (ref "U1") (pin "29") (pinfunction "VDDCORE_29") (pintype "power_in"))
    )
    (net (code "49") (name "Net-(U1-~{RESET})") (class "Default")
      (node (ref "S1") (pin "C") (pinfunction "NO_C") (pintype "passive"))
      (node (ref "S1") (pin "D") (pinfunction "NO_D") (pintype "passive"))
      (node (ref "U1") (pin "26") (pinfunction "~{RESET}_26") (pintype "passive"))
    )
    (net (code "50") (name "Net-(U2A-+)") (class "Default")
      (node (ref "C2") (pin "2") (pinfunction "2_2") (pintype "passive"))
      (node (ref "R3") (pin "2") (pinfunction "2_2") (pintype "passive"))
      (node (ref "R5") (pin "1") (pinfunction "1_1") (pintype "passive"))
      (node (ref "U2") (pin "3") (pinfunction "+_3") (pintype "bidirectional"))
    )
    (net (code "51") (name "Net-(U2A--)") (class "Default")
      (node (ref "R2") (pin "1") (pinfunction "1_1") (pintype "passive"))
      (node (ref "R4") (pin "1") (pinfunction "1_1") (pintype "passive"))
      (node (ref "U2") (pin "2") (pinfunction "-_2") (pintype "bidirectional"))
    )
    (net (code "52") (name "Net-(U2B--)") (class "Default")
      (node (ref "U2") (pin "6") (pinfunction "-_6") (pintype "bidirectional"))
      (node (ref "U2") (pin "7") (pinfunction "OUT_7") (pintype "bidirectional"))
    )
    (net (code "53") (name "Net-(U12-EN)") (class "Default")
      (node (ref "R13") (pin "2") (pinfunction "2_2") (pintype "passive"))
      (node (ref "U12") (pin "1") (pinfunction "PS/SYNC_1") (pintype "input"))
      (node (ref "U12") (pin "14") (pinfunction "EN_14") (pintype "input"))
    )
    (net (code "54") (name "Net-(U12-PG)") (class "Default")
      (node (ref "R15") (pin "2") (pinfunction "2_2") (pintype "passive"))
      (node (ref "U12") (pin "2") (pinfunction "PG_2") (pintype "output"))
    )
    (net (code "55") (name "Net-(U12-VAUX)") (class "Default")
      (node (ref "C20") (pin "1") (pinfunction "1_1") (pintype "passive"))
      (node (ref "U12") (pin "3") (pinfunction "VAUX_3") (pintype "output"))
    )
    (net (code "56") (name "V+") (class "Default")
      (node (ref "C15") (pin "1") (pinfunction "1_1") (pintype "passive"))
      (node (ref "C16") (pin "1") (pinfunction "1_1") (pintype "passive"))
      (node (ref "C17") (pin "1") (pinfunction "1_1") (pintype "passive"))
      (node (ref "C9") (pin "2") (pinfunction "2_2") (pintype "passive"))
      (node (ref "LED3") (pin "1-VDD") (pinfunction "VDD_1-VDD") (pintype "power_in"))
      (node (ref "LED4") (pin "1-VDD") (pinfunction "VDD_1-VDD") (pintype "power_in"))
      (node (ref "LED5") (pin "1-VDD") (pinfunction "VDD_1-VDD") (pintype "power_in"))
      (node (ref "LED6") (pin "1-VDD") (pinfunction "VDD_1-VDD") (pintype "power_in"))
      (node (ref "R15") (pin "1") (pinfunction "1_1") (pintype "passive"))
      (node (ref "U$3") (pin "6") (pinfunction "VDD_6") (pintype "power_in"))
      (node (ref "U12") (pin "5") (pinfunction "FB_5") (pintype "input"))
      (node (ref "U12") (pin "7_8") (pinfunction "VOUT_7_8") (pintype "output"))
    )
    (net (code "57") (name "unconnected-(LED6-DO-Pad2-DOUT)") (class "Default")
      (node (ref "LED6") (pin "2-DOUT") (pinfunction "DO_2-DOUT") (pintype "output"))
    )
    (net (code "58") (name "unconnected-(U1-PA01-Pad2)") (class "Default")
      (node (ref "U1") (pin "2") (pinfunction "PA01_2") (pintype "bidirectional"))
    )
    (net (code "59") (name "unconnected-(U1-PA03-Pad4)") (class "Default")
      (node (ref "U1") (pin "4") (pinfunction "PA03_4") (pintype "bidirectional"))
    )
    (net (code "60") (name "unconnected-(U1-PA04-Pad5)") (class "Default")
      (node (ref "U1") (pin "5") (pinfunction "PA04_5") (pintype "bidirectional"))
    )
    (net (code "61") (name "unconnected-(U1-PA05-Pad6)") (class "Default")
      (node (ref "U1") (pin "6") (pinfunction "PA05_6") (pintype "bidirectional"))
    )
    (net (code "62") (name "unconnected-(U1-PA11-Pad14)") (class "Default")
      (node (ref "U1") (pin "14") (pinfunction "PA11_14") (pintype "bidirectional"))
    )
    (net (code "63") (name "unconnected-(U1-PA22-Pad21)") (class "Default")
      (node (ref "U1") (pin "21") (pinfunction "PA22_21") (pintype "bidirectional"))
    )
    (net (code "64") (name "unconnected-(U1-PA23-Pad22)") (class "Default")
      (node (ref "U1") (pin "22") (pinfunction "PA23_22") (pintype "bidirectional"))
    )
    (net (code "65") (name "unconnected-(U1-PA27-Pad25)") (class "Default")
      (node (ref "U1") (pin "25") (pinfunction "PA27_25") (pintype "bidirectional"))
    )
    (net (code "66") (name "unconnected-(U1-PA28-Pad27)") (class "Default")
      (node (ref "U1") (pin "27") (pinfunction "PA28_27") (pintype "bidirectional"))
    )
    (net (code "67") (name "unconnected-(U4-Pad-)") (class "Default")
      (node (ref "U4") (pin "-") (pinfunction "-_-") (pintype "no_connect"))
    )
    (net (code "68") (name "unconnected-(U4-PadD)") (class "Default")
      (node (ref "U4") (pin "D") (pinfunction "D_D") (pintype "no_connect"))
    )
    (net (code "69") (name "unconnected-(U5-Pad-)") (class "Default")
      (node (ref "U5") (pin "-") (pinfunction "-_-") (pintype "no_connect"))
    )
    (net (code "70") (name "unconnected-(U5-PadD)") (class "Default")
      (node (ref "U5") (pin "D") (pinfunction "D_D") (pintype "no_connect"))
    )
    (net (code "71") (name "unconnected-(U6-Pad-)") (class "Default")
      (node (ref "U6") (pin "-") (pinfunction "-_-") (pintype "no_connect"))
    )
    (net (code "72") (name "unconnected-(U6-PadD)") (class "Default")
      (node (ref "U6") (pin "D") (pinfunction "D_D") (pintype "no_connect"))
    )
    (net (code "73") (name "unconnected-(U7-Pad-)") (class "Default")
      (node (ref "U7") (pin "-") (pinfunction "-_-") (pintype "no_connect"))
    )
    (net (code "74") (name "unconnected-(U7-PadD)") (class "Default")
      (node (ref "U7") (pin "D") (pinfunction "D_D") (pintype "no_connect"))
    )
    (net (code "75") (name "unconnected-(U8-Pad-)") (class "Default")
      (node (ref "U8") (pin "-") (pinfunction "-_-") (pintype "no_connect"))
    )
    (net (code "76") (name "unconnected-(U8-PadD)") (class "Default")
      (node (ref "U8") (pin "D") (pinfunction "D_D") (pintype "no_connect"))
    )
    (net (code "77") (name "unconnected-(U9-Pad-)") (class "Default")
      (node (ref "U9") (pin "-") (pinfunction "-_-") (pintype "no_connect"))
    )
    (net (code "78") (name "unconnected-(U9-PadD)") (class "Default")
      (node (ref "U9") (pin "D") (pinfunction "D_D") (pintype "no_connect"))
    )
    (net (code "79") (name "unconnected-(U10-Pad-)") (class "Default")
      (node (ref "U10") (pin "-") (pinfunction "-_-") (pintype "no_connect"))
    )
    (net (code "80") (name "unconnected-(U10-PadD)") (class "Default")
      (node (ref "U10") (pin "D") (pinfunction "D_D") (pintype "no_connect"))
    )
    (net (code "81") (name "unconnected-(U11-Pad-)") (class "Default")
      (node (ref "U11") (pin "-") (pinfunction "-_-") (pintype "no_connect"))
    )
    (net (code "82") (name "unconnected-(U11-PadD)") (class "Default")
      (node (ref "U11") (pin "D") (pinfunction "D_D") (pintype "no_connect"))
    )
  )
)
